# NT_RadioModule.net
KiCad netlist of a schematic drawn in EAGLE
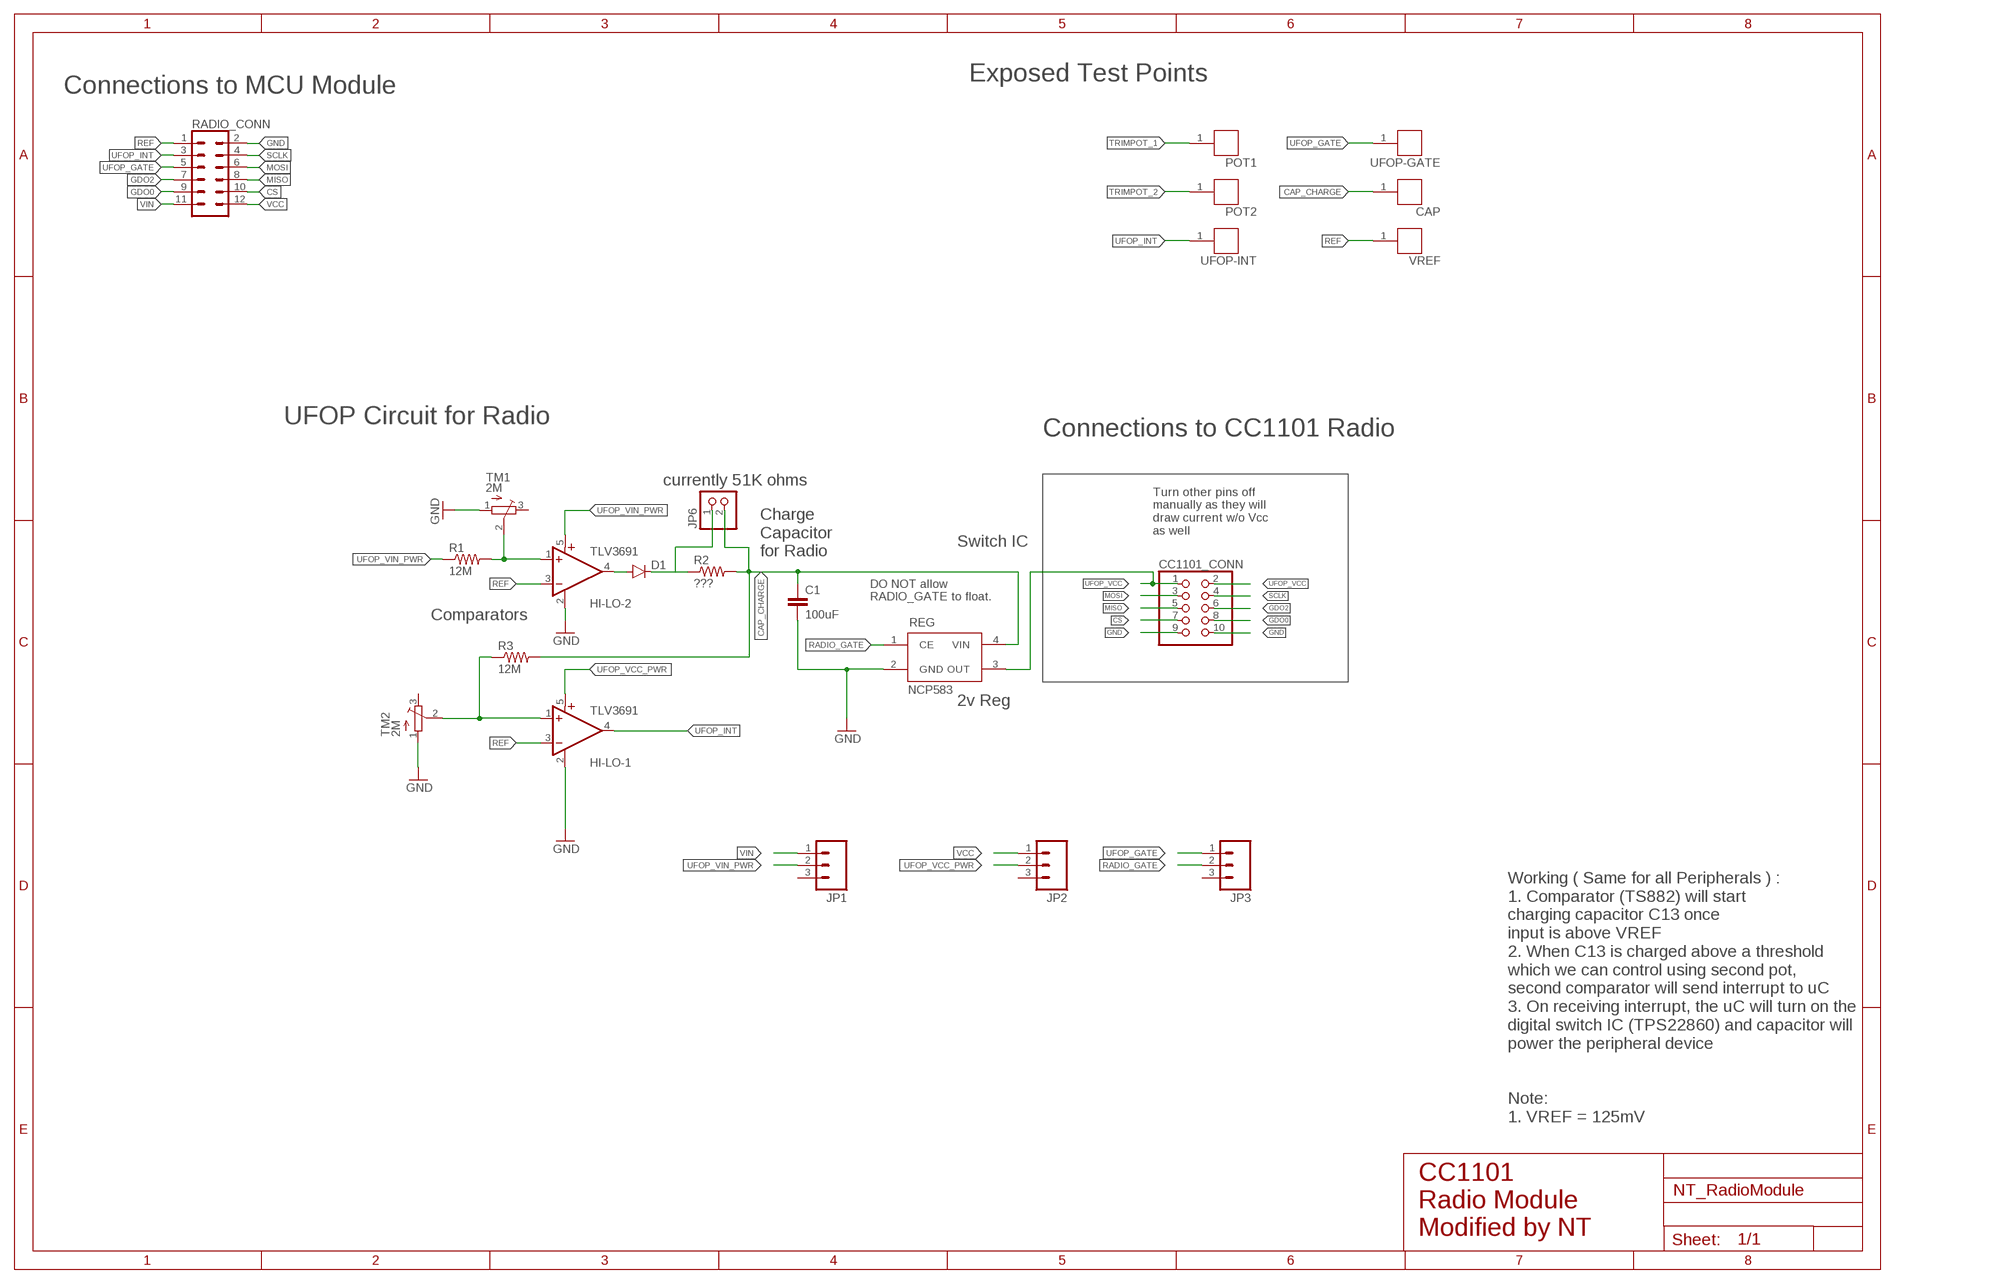
[diagram p0: schematic, sheet 1]

(export (version "E")
  (design (tool "Eeschema 10.0.6"))
  (components
    (comp (ref "C1")
      (value "100uF")
      (footprint "eagle-import:0603-CAP")
      (libsource (lib "eagle-import") (part "CAP0603-CAP"))
    )
    (comp (ref "CAP")
      (value "RCU-0C")
      (footprint "eagle-import:TE_RCU-0C")
      (fields
        (field (name "COMMENT") "RCU-0C _1625854-3_")
        (field (name "MF") "TE Connectivity")
        (field (name "TOLERANCE") "0%")
      )
      (libsource (lib "eagle-import") (part "RCU-0C"))
    )
    (comp (ref "CC1101_CONN")
      (value "PINHD-2X5")
      (footprint "eagle-import:2X05")
      (libsource (lib "eagle-import") (part "PINHD-2X5"))
    )
    (comp (ref "D1")
      (value "DIODESOD523")
      (footprint "eagle-import:SOD523")
      (libsource (lib "eagle-import") (part "DIODESOD523"))
    )
    (comp (ref "HI-LO-1")
      (value "TLV3691")
      (footprint "eagle-import:SC70-5")
      (libsource (lib "eagle-import") (part "TLV3691"))
    )
    (comp (ref "HI-LO-2")
      (value "TLV3691")
      (footprint "eagle-import:SC70-5")
      (libsource (lib "eagle-import") (part "TLV3691"))
    )
    (comp (ref "JP1")
      (value "M03")
      (footprint "eagle-import:1X03-1.27MM")
      (libsource (lib "eagle-import") (part "M03"))
    )
    (comp (ref "JP2")
      (value "M03")
      (footprint "eagle-import:1X03-1.27MM")
      (libsource (lib "eagle-import") (part "M03"))
    )
    (comp (ref "JP3")
      (value "M03")
      (footprint "eagle-import:1X03-1.27MM")
      (libsource (lib "eagle-import") (part "M03"))
    )
    (comp (ref "JP6")
      (value "PINHD-1X2")
      (footprint "eagle-import:1X02")
      (libsource (lib "eagle-import") (part "PINHD-1X2"))
    )
    (comp (ref "POT1")
      (value "RCU-0C")
      (footprint "eagle-import:TE_RCU-0C")
      (fields
        (field (name "COMMENT") "RCU-0C _1625854-3_")
        (field (name "MF") "TE Connectivity")
        (field (name "TOLERANCE") "0%")
      )
      (libsource (lib "eagle-import") (part "RCU-0C"))
    )
    (comp (ref "POT2")
      (value "RCU-0C")
      (footprint "eagle-import:TE_RCU-0C")
      (fields
        (field (name "COMMENT") "RCU-0C _1625854-3_")
        (field (name "MF") "TE Connectivity")
        (field (name "TOLERANCE") "0%")
      )
      (libsource (lib "eagle-import") (part "RCU-0C"))
    )
    (comp (ref "R1")
      (value "12M")
      (footprint "eagle-import:0603-RES")
      (libsource (lib "eagle-import") (part "RESISTOR0603"))
    )
    (comp (ref "R2")
      (value "???")
      (footprint "eagle-import:0603-RES")
      (libsource (lib "eagle-import") (part "RESISTOR0603"))
    )
    (comp (ref "R3")
      (value "12M")
      (footprint "eagle-import:0603-RES")
      (libsource (lib "eagle-import") (part "RESISTOR0603"))
    )
    (comp (ref "RADIO_CONN")
      (value "CONN_06X2PTH_FEMALE")
      (footprint "eagle-import:2X6")
      (libsource (lib "eagle-import") (part "CONN_06X2PTH_FEMALE"))
    )
    (comp (ref "REG")
      (value "NCP583")
      (footprint "eagle-import:SC82-AB_1PRIMARY")
      (libsource (lib "eagle-import") (part "NCP583"))
    )
    (comp (ref "TM1")
      (value "2M")
      (footprint "eagle-import:TC33X")
      (libsource (lib "eagle-import") (part "TRIMPOTTC33X"))
    )
    (comp (ref "TM2")
      (value "2M")
      (footprint "eagle-import:TC33X")
      (libsource (lib "eagle-import") (part "TRIMPOTTC33X"))
    )
    (comp (ref "UFOP-GATE")
      (value "RCU-0C")
      (footprint "eagle-import:TE_RCU-0C")
      (fields
        (field (name "COMMENT") "RCU-0C _1625854-3_")
        (field (name "MF") "TE Connectivity")
        (field (name "TOLERANCE") "0%")
      )
      (libsource (lib "eagle-import") (part "RCU-0C"))
    )
    (comp (ref "UFOP-INT")
      (value "RCU-0C")
      (footprint "eagle-import:TE_RCU-0C")
      (fields
        (field (name "COMMENT") "RCU-0C _1625854-3_")
        (field (name "MF") "TE Connectivity")
        (field (name "TOLERANCE") "0%")
      )
      (libsource (lib "eagle-import") (part "RCU-0C"))
    )
    (comp (ref "VREF")
      (value "RCU-0C")
      (footprint "eagle-import:TE_RCU-0C")
      (fields
        (field (name "COMMENT") "RCU-0C _1625854-3_")
        (field (name "MF") "TE Connectivity")
        (field (name "TOLERANCE") "0%")
      )
      (libsource (lib "eagle-import") (part "RCU-0C"))
    )
  )
  (nets
    (net (code "1") (name "CAP_CHARGE") (class "Default")
      (node (ref "C1") (pin "1") (pinfunction "1_1") (pintype "passive"))
      (node (ref "CAP") (pin "1") (pinfunction "1_1") (pintype "passive"))
      (node (ref "JP6") (pin "2") (pinfunction "2_2") (pintype "passive"))
      (node (ref "R2") (pin "2") (pinfunction "2_2") (pintype "passive"))
      (node (ref "R3") (pin "2") (pinfunction "2_2") (pintype "passive"))
      (node (ref "REG") (pin "4") (pinfunction "VIN_4") (pintype "bidirectional"))
    )
    (net (code "2") (name "CS") (class "Default")
      (node (ref "CC1101_CONN") (pin "7") (pinfunction "7_7") (pintype "passive"))
      (node (ref "RADIO_CONN") (pin "10") (pinfunction "10_10") (pintype "passive"))
    )
    (net (code "3") (name "GDO0") (class "Default")
      (node (ref "CC1101_CONN") (pin "8") (pinfunction "8_8") (pintype "passive"))
      (node (ref "RADIO_CONN") (pin "9") (pinfunction "9_9") (pintype "passive"))
    )
    (net (code "4") (name "GDO2") (class "Default")
      (node (ref "CC1101_CONN") (pin "6") (pinfunction "6_6") (pintype "passive"))
      (node (ref "RADIO_CONN") (pin "7") (pinfunction "7_7") (pintype "passive"))
    )
    (net (code "5") (name "GND") (class "Default")
      (node (ref "C1") (pin "2") (pinfunction "2_2") (pintype "passive"))
      (node (ref "CC1101_CONN") (pin "10") (pinfunction "10_10") (pintype "passive"))
      (node (ref "CC1101_CONN") (pin "9") (pinfunction "9_9") (pintype "passive"))
      (node (ref "HI-LO-1") (pin "2") (pinfunction "GND_2") (pintype "power_in"))
      (node (ref "HI-LO-2") (pin "2") (pinfunction "GND_2") (pintype "power_in"))
      (node (ref "RADIO_CONN") (pin "2") (pinfunction "2_2") (pintype "passive"))
      (node (ref "REG") (pin "2") (pinfunction "GND_2") (pintype "bidirectional"))
      (node (ref "TM1") (pin "1") (pinfunction "A_1") (pintype "passive"))
      (node (ref "TM2") (pin "1") (pinfunction "A_1") (pintype "passive"))
    )
    (net (code "6") (name "MISO") (class "Default")
      (node (ref "CC1101_CONN") (pin "5") (pinfunction "5_5") (pintype "passive"))
      (node (ref "RADIO_CONN") (pin "8") (pinfunction "8_8") (pintype "passive"))
    )
    (net (code "7") (name "MOSI") (class "Default")
      (node (ref "CC1101_CONN") (pin "3") (pinfunction "3_3") (pintype "passive"))
      (node (ref "RADIO_CONN") (pin "6") (pinfunction "6_6") (pintype "passive"))
    )
    (net (code "8") (name "Net-(D1-PadC)") (class "Default")
      (node (ref "D1") (pin "C") (pinfunction "C_C") (pintype "passive"))
      (node (ref "JP6") (pin "1") (pinfunction "1_1") (pintype "passive"))
      (node (ref "R2") (pin "1") (pinfunction "1_1") (pintype "passive"))
    )
    (net (code "9") (name "Net-(HI-LO-2-OUT)") (class "Default")
      (node (ref "D1") (pin "A") (pinfunction "A_A") (pintype "passive"))
      (node (ref "HI-LO-2") (pin "4") (pinfunction "OUT_4") (pintype "output"))
    )
    (net (code "10") (name "RADIO_GATE") (class "Default")
      (node (ref "JP3") (pin "2") (pinfunction "2_2") (pintype "passive"))
      (node (ref "REG") (pin "1") (pinfunction "CE_1") (pintype "bidirectional"))
    )
    (net (code "11") (name "REF") (class "Default")
      (node (ref "HI-LO-1") (pin "3") (pinfunction "-IN_3") (pintype "input"))
      (node (ref "HI-LO-2") (pin "3") (pinfunction "-IN_3") (pintype "input"))
      (node (ref "RADIO_CONN") (pin "1") (pinfunction "1_1") (pintype "passive"))
      (node (ref "VREF") (pin "1") (pinfunction "1_1") (pintype "passive"))
    )
    (net (code "12") (name "SCLK") (class "Default")
      (node (ref "CC1101_CONN") (pin "4") (pinfunction "4_4") (pintype "passive"))
      (node (ref "RADIO_CONN") (pin "4") (pinfunction "4_4") (pintype "passive"))
    )
    (net (code "13") (name "TRIMPOT_1") (class "Default")
      (node (ref "HI-LO-2") (pin "1") (pinfunction "+IN_1") (pintype "input"))
      (node (ref "POT1") (pin "1") (pinfunction "1_1") (pintype "passive"))
      (node (ref "R1") (pin "2") (pinfunction "2_2") (pintype "passive"))
      (node (ref "TM1") (pin "2") (pinfunction "S_2") (pintype "passive"))
    )
    (net (code "14") (name "TRIMPOT_2") (class "Default")
      (node (ref "HI-LO-1") (pin "1") (pinfunction "+IN_1") (pintype "input"))
      (node (ref "POT2") (pin "1") (pinfunction "1_1") (pintype "passive"))
      (node (ref "R3") (pin "1") (pinfunction "1_1") (pintype "passive"))
      (node (ref "TM2") (pin "2") (pinfunction "S_2") (pintype "passive"))
    )
    (net (code "15") (name "UFOP_GATE") (class "Default")
      (node (ref "JP3") (pin "1") (pinfunction "1_1") (pintype "passive"))
      (node (ref "RADIO_CONN") (pin "5") (pinfunction "5_5") (pintype "passive"))
      (node (ref "UFOP-GATE") (pin "1") (pinfunction "1_1") (pintype "passive"))
    )
    (net (code "16") (name "UFOP_INT") (class "Default")
      (node (ref "HI-LO-1") (pin "4") (pinfunction "OUT_4") (pintype "output"))
      (node (ref "RADIO_CONN") (pin "3") (pinfunction "3_3") (pintype "passive"))
      (node (ref "UFOP-INT") (pin "1") (pinfunction "1_1") (pintype "passive"))
    )
    (net (code "17") (name "UFOP_VCC") (class "Default")
      (node (ref "CC1101_CONN") (pin "1") (pinfunction "1_1") (pintype "passive"))
      (node (ref "CC1101_CONN") (pin "2") (pinfunction "2_2") (pintype "passive"))
      (node (ref "REG") (pin "3") (pinfunction "OUT_3") (pintype "bidirectional"))
    )
    (net (code "18") (name "UFOP_VCC_PWR") (class "Default")
      (node (ref "HI-LO-1") (pin "5") (pinfunction "V+_5") (pintype "power_in"))
      (node (ref "JP2") (pin "2") (pinfunction "2_2") (pintype "passive"))
    )
    (net (code "19") (name "UFOP_VIN_PWR") (class "Default")
      (node (ref "HI-LO-2") (pin "5") (pinfunction "V+_5") (pintype "power_in"))
      (node (ref "JP1") (pin "2") (pinfunction "2_2") (pintype "passive"))
      (node (ref "R1") (pin "1") (pinfunction "1_1") (pintype "passive"))
    )
    (net (code "20") (name "VCC") (class "Default")
      (node (ref "JP2") (pin "1") (pinfunction "1_1") (pintype "passive"))
      (node (ref "RADIO_CONN") (pin "12") (pinfunction "12_12") (pintype "passive"))
    )
    (net (code "21") (name "VIN") (class "Default")
      (node (ref "JP1") (pin "1") (pinfunction "1_1") (pintype "passive"))
      (node (ref "RADIO_CONN") (pin "11") (pinfunction "11_11") (pintype "passive"))
    )
    (net (code "22") (name "unconnected-(JP1-Pad3)") (class "Default")
      (node (ref "JP1") (pin "3") (pinfunction "3_3") (pintype "passive"))
    )
    (net (code "23") (name "unconnected-(JP2-Pad3)") (class "Default")
      (node (ref "JP2") (pin "3") (pinfunction "3_3") (pintype "passive"))
    )
    (net (code "24") (name "unconnected-(JP3-Pad3)") (class "Default")
      (node (ref "JP3") (pin "3") (pinfunction "3_3") (pintype "passive"))
    )
    (net (code "25") (name "unconnected-(TM1-E-Pad3)") (class "Default")
      (node (ref "TM1") (pin "3") (pinfunction "E_3") (pintype "passive"))
    )
    (net (code "26") (name "unconnected-(TM2-E-Pad3)") (class "Default")
      (node (ref "TM2") (pin "3") (pinfunction "E_3") (pintype "passive"))
    )
  )
)
